# Sheet1-MCU.net
KiCad netlist of a schematic drawn in Altium Designer
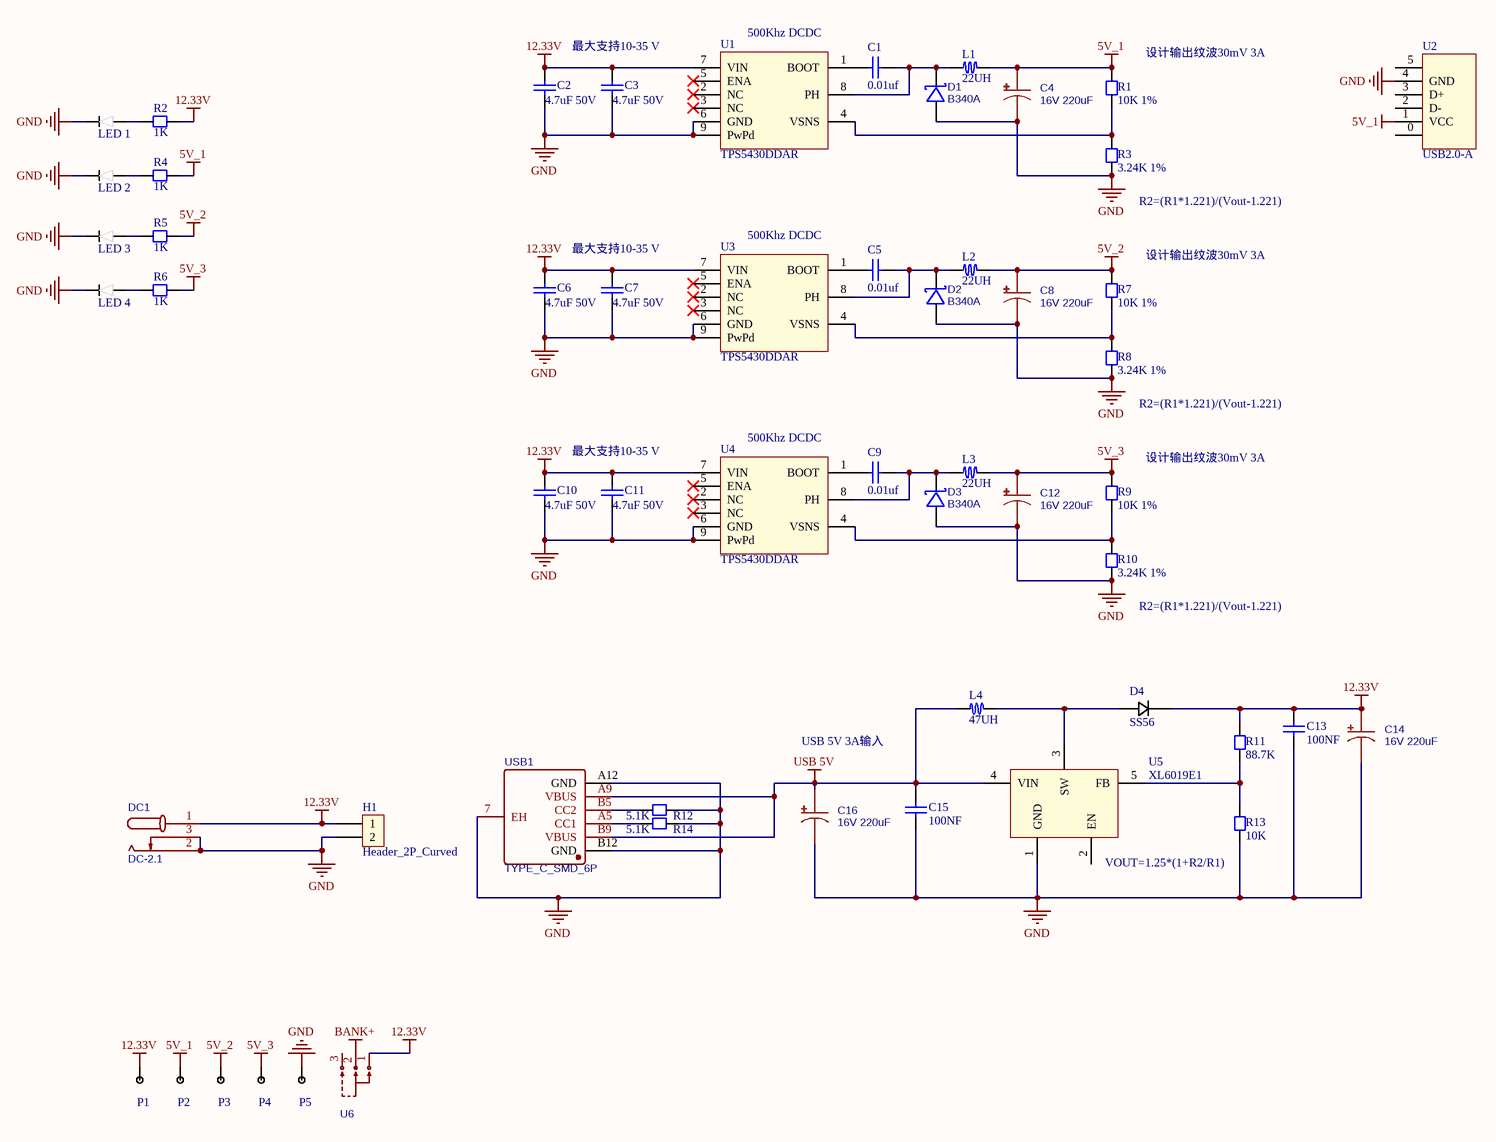
[diagram p0: Sheet1-MCU.SchDoc]

(export (version "E")
  (design (tool "Eeschema 10.0.6"))
  (components
    (comp (ref "C1")
      (value "0.01uf")
      (footprint "CC1608-0603")
      (description "贴片电容")
      (libsource (lib "tianxiaohua_Schlib") (part "Chip capacitor"))
    )
    (comp (ref "C2")
      (value "4.7uF 50V")
      (footprint "CC1608-0603")
      (description "贴片电容")
      (libsource (lib "tianxiaohua_Schlib") (part "Chip capacitor"))
    )
    (comp (ref "C3")
      (value "4.7uF 50V")
      (footprint "CC1608-0603")
      (description "贴片电容")
      (libsource (lib "tianxiaohua_Schlib") (part "Chip capacitor"))
    )
    (comp (ref "C4")
      (value "16V 220uF")
      (footprint "CAP-SMD_D6.3")
      (description "铝点解电容")
      (fields
        (field (name "BOM_SUPPLIER PART") "C413527")
        (field (name "BOM_MANUFACTURER PART") "EEEFP1C681AP")
        (field (name "CONTRIBUTOR") "LCSC")
      )
      (libsource (lib "base") (part "Cap ECAP SMD"))
    )
    (comp (ref "C5")
      (value "0.01uf")
      (footprint "CC1608-0603")
      (description "贴片电容")
      (libsource (lib "tianxiaohua_Schlib") (part "Chip capacitor"))
    )
    (comp (ref "C6")
      (value "4.7uF 50V")
      (footprint "CC1608-0603")
      (description "贴片电容")
      (libsource (lib "tianxiaohua_Schlib") (part "Chip capacitor"))
    )
    (comp (ref "C7")
      (value "4.7uF 50V")
      (footprint "CC1608-0603")
      (description "贴片电容")
      (libsource (lib "tianxiaohua_Schlib") (part "Chip capacitor"))
    )
    (comp (ref "C8")
      (value "16V 220uF")
      (footprint "CAP-SMD_D6.3")
      (description "铝点解电容")
      (fields
        (field (name "BOM_SUPPLIER PART") "C413527")
        (field (name "BOM_MANUFACTURER PART") "EEEFP1C681AP")
        (field (name "CONTRIBUTOR") "LCSC")
      )
      (libsource (lib "base") (part "Cap ECAP SMD"))
    )
    (comp (ref "C9")
      (value "0.01uf")
      (footprint "CC1608-0603")
      (description "贴片电容")
      (libsource (lib "tianxiaohua_Schlib") (part "Chip capacitor"))
    )
    (comp (ref "C10")
      (value "4.7uF 50V")
      (footprint "CC1608-0603")
      (description "贴片电容")
      (libsource (lib "tianxiaohua_Schlib") (part "Chip capacitor"))
    )
    (comp (ref "C11")
      (value "4.7uF 50V")
      (footprint "CC1608-0603")
      (description "贴片电容")
      (libsource (lib "tianxiaohua_Schlib") (part "Chip capacitor"))
    )
    (comp (ref "C12")
      (value "16V 220uF")
      (footprint "CAP-SMD_D6.3")
      (description "铝点解电容")
      (fields
        (field (name "BOM_SUPPLIER PART") "C413527")
        (field (name "BOM_MANUFACTURER PART") "EEEFP1C681AP")
        (field (name "CONTRIBUTOR") "LCSC")
      )
      (libsource (lib "base") (part "Cap ECAP SMD"))
    )
    (comp (ref "C13")
      (value "100NF")
      (footprint "CC1608-0603")
      (description "0603封装的电容")
      (fields (field (name "PUBLISHER") "Altium Limited"))
      (libsource (lib "base") (part "Cap Chip 0603"))
    )
    (comp (ref "C14")
      (value "16V 220uF")
      (footprint "CAP-SMD_D6.3")
      (description "铝点解电容")
      (fields
        (field (name "BOM_SUPPLIER PART") "C413527")
        (field (name "BOM_MANUFACTURER PART") "EEEFP1C681AP")
        (field (name "CONTRIBUTOR") "LCSC")
      )
      (libsource (lib "base") (part "Cap ECAP SMD"))
    )
    (comp (ref "C15")
      (value "100NF")
      (footprint "CC1608-0603")
      (description "0603封装的电容")
      (fields (field (name "PUBLISHER") "Altium Limited"))
      (libsource (lib "base") (part "Cap Chip 0603"))
    )
    (comp (ref "C16")
      (value "16V 220uF")
      (footprint "CAP-SMD_D6.3")
      (description "铝点解电容")
      (fields
        (field (name "BOM_SUPPLIER PART") "C413527")
        (field (name "BOM_MANUFACTURER PART") "EEEFP1C681AP")
        (field (name "CONTRIBUTOR") "LCSC")
      )
      (libsource (lib "base") (part "Cap ECAP SMD"))
    )
    (comp (ref "D1")
      (value "B340A")
      (footprint "DO-214 AA")
      (description "40V 3A 550mV@3A")
      (fields (field (name "BOM_SUPPLIER PART") "C64982"))
      (libsource (lib "transistor") (part "B340A"))
    )
    (comp (ref "D2")
      (value "B340A")
      (footprint "DO-214 AA")
      (description "40V 3A 550mV@3A")
      (fields (field (name "BOM_SUPPLIER PART") "C64982"))
      (libsource (lib "transistor") (part "B340A"))
    )
    (comp (ref "D3")
      (value "B340A")
      (footprint "DO-214 AA")
      (description "40V 3A 550mV@3A")
      (fields (field (name "BOM_SUPPLIER PART") "C64982"))
      (libsource (lib "transistor") (part "B340A"))
    )
    (comp (ref "D4")
      (value "SS56")
      (footprint "DO-214 AA")
      (description "肖特基二极管")
      (libsource (lib "transistor") (part "SS34"))
    )
    (comp (ref "DC1")
      (value "DC-2.1")
      (footprint "DC-IN-SMD_DC-050-25A")
      (description "DC贴片插座")
      (fields
        (field (name "BOM_SUPPLIER PART") "C707275")
        (field (name "BOM_MANUFACTURER PART") "DC-050-25A")
        (field (name "CONTRIBUTOR") "LCSC")
      )
      (libsource (lib "Connectors") (part "DC-050"))
    )
    (comp (ref "H1")
      (value "Header_2P_Curved")
      (footprint "Header_2_54_2PW")
      (description "弯的2P排针")
      (libsource (lib "base") (part "Header_2P_Curved"))
    )
    (comp (ref "L1")
      (value "22UH")
      (footprint "Inductor-1040")
      (description "1040封装 一体成型 贴片 功率电感")
      (libsource (lib "base") (part "Inductor-1040"))
    )
    (comp (ref "L2")
      (value "22UH")
      (footprint "Inductor-1040")
      (description "1040封装 一体成型 贴片 功率电感")
      (libsource (lib "base") (part "Inductor-1040"))
    )
    (comp (ref "L3")
      (value "22UH")
      (footprint "Inductor-1040")
      (description "1040封装 一体成型 贴片 功率电感")
      (libsource (lib "base") (part "Inductor-1040"))
    )
    (comp (ref "L4")
      (value "47UH")
      (footprint "Inductor-1040")
      (description "1040封装 一体成型 贴片 功率电感")
      (libsource (lib "base") (part "Inductor-1040"))
    )
    (comp (ref "LED 1") (value "LED 0603") (footprint "LED 0603") (libsource (lib "base") (part "LED 0603")))
    (comp (ref "LED 2") (value "LED 0603") (footprint "LED 0603") (libsource (lib "base") (part "LED 0603")))
    (comp (ref "LED 3") (value "LED 0603") (footprint "LED 0603") (libsource (lib "base") (part "LED 0603")))
    (comp (ref "LED 4") (value "LED 0603") (footprint "LED 0603") (libsource (lib "base") (part "LED 0603")))
    (comp (ref "P1")
      (value "pogopin")
      (footprint "pogopin")
      (description "插板式顶针 连接器弹簧天线插针SMT触点测试铜针双弹贴片式")
      (libsource (lib "Connectors") (part "pogopin"))
    )
    (comp (ref "P2")
      (value "pogopin")
      (footprint "pogopin")
      (description "插板式顶针 连接器弹簧天线插针SMT触点测试铜针双弹贴片式")
      (libsource (lib "Connectors") (part "pogopin"))
    )
    (comp (ref "P3")
      (value "pogopin")
      (footprint "pogopin")
      (description "插板式顶针 连接器弹簧天线插针SMT触点测试铜针双弹贴片式")
      (libsource (lib "Connectors") (part "pogopin"))
    )
    (comp (ref "P4")
      (value "pogopin")
      (footprint "pogopin")
      (description "插板式顶针 连接器弹簧天线插针SMT触点测试铜针双弹贴片式")
      (libsource (lib "Connectors") (part "pogopin"))
    )
    (comp (ref "P5")
      (value "pogopin")
      (footprint "pogopin")
      (description "插板式顶针 连接器弹簧天线插针SMT触点测试铜针双弹贴片式")
      (libsource (lib "Connectors") (part "pogopin"))
    )
    (comp (ref "R1")
      (value "10K 1%")
      (footprint "CR1608-0603")
      (description "贴片电阻")
      (libsource (lib "tianxiaohua_Schlib") (part "Chip resistor"))
    )
    (comp (ref "R2")
      (value "1K")
      (footprint "CR1608-0603")
      (description "0603封装电阻")
      (fields (field (name "PUBLISHER") "Altium Limited"))
      (libsource (lib "base") (part "Resistor Chip 0603"))
    )
    (comp (ref "R3")
      (value "3.24K 1%")
      (footprint "CR1608-0603")
      (description "贴片电阻")
      (libsource (lib "tianxiaohua_Schlib") (part "Chip resistor"))
    )
    (comp (ref "R4")
      (value "1K")
      (footprint "CR1608-0603")
      (description "0603封装电阻")
      (fields (field (name "PUBLISHER") "Altium Limited"))
      (libsource (lib "base") (part "Resistor Chip 0603"))
    )
    (comp (ref "R5")
      (value "1K")
      (footprint "CR1608-0603")
      (description "0603封装电阻")
      (fields (field (name "PUBLISHER") "Altium Limited"))
      (libsource (lib "base") (part "Resistor Chip 0603"))
    )
    (comp (ref "R6")
      (value "1K")
      (footprint "CR1608-0603")
      (description "0603封装电阻")
      (fields (field (name "PUBLISHER") "Altium Limited"))
      (libsource (lib "base") (part "Resistor Chip 0603"))
    )
    (comp (ref "R7")
      (value "10K 1%")
      (footprint "CR1608-0603")
      (description "贴片电阻")
      (libsource (lib "tianxiaohua_Schlib") (part "Chip resistor"))
    )
    (comp (ref "R8")
      (value "3.24K 1%")
      (footprint "CR1608-0603")
      (description "贴片电阻")
      (libsource (lib "tianxiaohua_Schlib") (part "Chip resistor"))
    )
    (comp (ref "R9")
      (value "10K 1%")
      (footprint "CR1608-0603")
      (description "贴片电阻")
      (libsource (lib "tianxiaohua_Schlib") (part "Chip resistor"))
    )
    (comp (ref "R10")
      (value "3.24K 1%")
      (footprint "CR1608-0603")
      (description "贴片电阻")
      (libsource (lib "tianxiaohua_Schlib") (part "Chip resistor"))
    )
    (comp (ref "R11")
      (value "88.7K")
      (footprint "CR1608-0603")
      (description "0603封装电阻")
      (fields (field (name "PUBLISHER") "Altium Limited"))
      (libsource (lib "") (part "Resistor Chip 0603_2"))
    )
    (comp (ref "R12")
      (value "5.1K")
      (footprint "CR1608-0603")
      (description "0603封装电阻")
      (fields (field (name "PUBLISHER") "Altium Limited"))
      (libsource (lib "") (part "Resistor Chip 0603_1"))
    )
    (comp (ref "R13")
      (value "10K")
      (footprint "CR1608-0603")
      (description "0603封装电阻")
      (fields (field (name "PUBLISHER") "Altium Limited"))
      (libsource (lib "") (part "Resistor Chip 0603_2"))
    )
    (comp (ref "R14")
      (value "5.1K")
      (footprint "CR1608-0603")
      (description "0603封装电阻")
      (fields (field (name "PUBLISHER") "Altium Limited"))
      (libsource (lib "") (part "Resistor Chip 0603_1"))
    )
    (comp (ref "U1")
      (value "TPS5430DDAR")
      (footprint "SOIC-8-E")
      (description "宽电压DCDC降压IC")
      (libsource (lib "power-chip") (part "TPS5430DDAR"))
    )
    (comp (ref "U2")
      (value "USB2.0-A")
      (footprint "USB2.0-A")
      (description "USB母座")
      (libsource (lib "Connectors") (part "USB2.0-A"))
    )
    (comp (ref "U3")
      (value "TPS5430DDAR")
      (footprint "SOIC-8-E")
      (description "宽电压DCDC降压IC")
      (libsource (lib "power-chip") (part "TPS5430DDAR"))
    )
    (comp (ref "U4")
      (value "TPS5430DDAR")
      (footprint "SOIC-8-E")
      (description "宽电压DCDC降压IC")
      (libsource (lib "power-chip") (part "TPS5430DDAR"))
    )
    (comp (ref "U5")
      (value "XL6019E1")
      (footprint "TO-263-5")
      (description "升压芯片 5A最大输出")
      (libsource (lib "power-chip") (part "XL6019E1"))
    )
    (comp (ref "U6")
      (value "HX SS12D10G4")
      (footprint "SW-TH_3P-SS12D06")
      (fields (field (name "BOM_SUPPLIER PART") "C5149841") (field (name "CONTRIBUTOR") "lcsc"))
      (libsource (lib "base") (part "SW-TH_3P-SS12D06"))
    )
    (comp (ref "USB1")
      (value "TYPE_C_SMD_6P")
      (footprint "TYPE-C-SMD_TYPE-C-6P")
      (fields (field (name "CONTRIBUTOR") "LCSC"))
      (libsource (lib "Connectors") (part "TYPE_C_SMD_6P"))
    )
  )
  (nets
    (net (code "1") (name "5V_1") (class "Default")
      (node (ref "C4") (pin "1") (pinfunction "1_1") (pintype "passive"))
      (node (ref "L1") (pin "2") (pinfunction "2_2") (pintype "passive"))
      (node (ref "P2") (pin "1") (pinfunction "1_1") (pintype "passive"))
      (node (ref "R1") (pin "2") (pinfunction "2_2") (pintype "passive"))
      (node (ref "R4") (pin "1") (pinfunction "1_1") (pintype "passive"))
      (node (ref "U2") (pin "1") (pinfunction "VCC_1") (pintype "passive"))
    )
    (net (code "2") (name "5V_2") (class "Default")
      (node (ref "C8") (pin "1") (pinfunction "1_1") (pintype "passive"))
      (node (ref "L2") (pin "2") (pinfunction "2_2") (pintype "passive"))
      (node (ref "P3") (pin "1") (pinfunction "1_1") (pintype "passive"))
      (node (ref "R5") (pin "1") (pinfunction "1_1") (pintype "passive"))
      (node (ref "R7") (pin "2") (pinfunction "2_2") (pintype "passive"))
    )
    (net (code "3") (name "5V_3") (class "Default")
      (node (ref "C12") (pin "1") (pinfunction "1_1") (pintype "passive"))
      (node (ref "L3") (pin "2") (pinfunction "2_2") (pintype "passive"))
      (node (ref "P4") (pin "1") (pinfunction "1_1") (pintype "passive"))
      (node (ref "R6") (pin "1") (pinfunction "1_1") (pintype "passive"))
      (node (ref "R9") (pin "2") (pinfunction "2_2") (pintype "passive"))
    )
    (net (code "4") (name "12.33V") (class "Default")
      (node (ref "C10") (pin "1") (pinfunction "1_1") (pintype "passive"))
      (node (ref "C11") (pin "1") (pinfunction "1_1") (pintype "passive"))
      (node (ref "C13") (pin "2") (pinfunction "2_2") (pintype "passive"))
      (node (ref "C14") (pin "1") (pinfunction "1_1") (pintype "passive"))
      (node (ref "C2") (pin "1") (pinfunction "1_1") (pintype "passive"))
      (node (ref "C3") (pin "1") (pinfunction "1_1") (pintype "passive"))
      (node (ref "C6") (pin "1") (pinfunction "1_1") (pintype "passive"))
      (node (ref "C7") (pin "1") (pinfunction "1_1") (pintype "passive"))
      (node (ref "D4") (pin "1") (pinfunction "K_1") (pintype "passive"))
      (node (ref "DC1") (pin "1") (pinfunction "1_1") (pintype "passive"))
      (node (ref "H1") (pin "1") (pinfunction "1_1") (pintype "passive"))
      (node (ref "P1") (pin "1") (pinfunction "1_1") (pintype "passive"))
      (node (ref "R11") (pin "2") (pinfunction "2_2") (pintype "passive"))
      (node (ref "R2") (pin "1") (pinfunction "1_1") (pintype "passive"))
      (node (ref "U1") (pin "7") (pinfunction "VIN_7") (pintype "passive"))
      (node (ref "U3") (pin "7") (pinfunction "VIN_7") (pintype "passive"))
      (node (ref "U4") (pin "7") (pinfunction "VIN_7") (pintype "passive"))
      (node (ref "U6") (pin "1") (pinfunction "1_1") (pintype "passive"))
    )
    (net (code "5") (name "BANK+") (class "Default")
      (node (ref "U6") (pin "2") (pinfunction "2_2") (pintype "passive"))
    )
    (net (code "6") (name "GND") (class "Default")
      (node (ref "C10") (pin "2") (pinfunction "2_2") (pintype "passive"))
      (node (ref "C11") (pin "2") (pinfunction "2_2") (pintype "passive"))
      (node (ref "C12") (pin "2") (pinfunction "2_2") (pintype "passive"))
      (node (ref "C13") (pin "1") (pinfunction "1_1") (pintype "passive"))
      (node (ref "C14") (pin "2") (pinfunction "2_2") (pintype "passive"))
      (node (ref "C15") (pin "1") (pinfunction "1_1") (pintype "passive"))
      (node (ref "C16") (pin "2") (pinfunction "2_2") (pintype "passive"))
      (node (ref "C2") (pin "2") (pinfunction "2_2") (pintype "passive"))
      (node (ref "C3") (pin "2") (pinfunction "2_2") (pintype "passive"))
      (node (ref "C4") (pin "2") (pinfunction "2_2") (pintype "passive"))
      (node (ref "C6") (pin "2") (pinfunction "2_2") (pintype "passive"))
      (node (ref "C7") (pin "2") (pinfunction "2_2") (pintype "passive"))
      (node (ref "C8") (pin "2") (pinfunction "2_2") (pintype "passive"))
      (node (ref "D1") (pin "2") (pinfunction "A_2") (pintype "passive"))
      (node (ref "D2") (pin "2") (pinfunction "A_2") (pintype "passive"))
      (node (ref "D3") (pin "2") (pinfunction "A_2") (pintype "passive"))
      (node (ref "DC1") (pin "2") (pinfunction "2_2") (pintype "passive"))
      (node (ref "DC1") (pin "3") (pinfunction "3_3") (pintype "passive"))
      (node (ref "H1") (pin "2") (pinfunction "2_2") (pintype "passive"))
      (node (ref "LED 1") (pin "2") (pinfunction "2_2") (pintype "passive"))
      (node (ref "LED 2") (pin "2") (pinfunction "2_2") (pintype "passive"))
      (node (ref "LED 3") (pin "2") (pinfunction "2_2") (pintype "passive"))
      (node (ref "LED 4") (pin "2") (pinfunction "2_2") (pintype "passive"))
      (node (ref "P5") (pin "1") (pinfunction "1_1") (pintype "passive"))
      (node (ref "R10") (pin "1") (pinfunction "1_1") (pintype "passive"))
      (node (ref "R12") (pin "2") (pinfunction "2_2") (pintype "passive"))
      (node (ref "R13") (pin "1") (pinfunction "1_1") (pintype "passive"))
      (node (ref "R14") (pin "2") (pinfunction "2_2") (pintype "passive"))
      (node (ref "R3") (pin "1") (pinfunction "1_1") (pintype "passive"))
      (node (ref "R8") (pin "1") (pinfunction "1_1") (pintype "passive"))
      (node (ref "U1") (pin "6") (pinfunction "GND_6") (pintype "passive"))
      (node (ref "U1") (pin "9") (pinfunction "PwPd_9") (pintype "passive"))
      (node (ref "U2") (pin "4") (pinfunction "GND_4") (pintype "passive"))
      (node (ref "U3") (pin "6") (pinfunction "GND_6") (pintype "passive"))
      (node (ref "U3") (pin "9") (pinfunction "PwPd_9") (pintype "passive"))
      (node (ref "U4") (pin "6") (pinfunction "GND_6") (pintype "passive"))
      (node (ref "U4") (pin "9") (pinfunction "PwPd_9") (pintype "passive"))
      (node (ref "U5") (pin "1") (pinfunction "GND_1") (pintype "passive"))
      (node (ref "USB1") (pin "7") (pinfunction "EH_7") (pintype "passive"))
      (node (ref "USB1") (pin "A12") (pinfunction "GND_A12") (pintype "passive"))
      (node (ref "USB1") (pin "B12") (pinfunction "GND_B12") (pintype "passive"))
    )
    (net (code "7") (name "Net-(D1-K)") (class "Default")
      (node (ref "C1") (pin "2") (pinfunction "2_2") (pintype "passive"))
      (node (ref "D1") (pin "1") (pinfunction "K_1") (pintype "passive"))
      (node (ref "L1") (pin "1") (pinfunction "1_1") (pintype "passive"))
      (node (ref "U1") (pin "8") (pinfunction "PH_8") (pintype "passive"))
    )
    (net (code "8") (name "Net-(D2-K)") (class "Default")
      (node (ref "C5") (pin "2") (pinfunction "2_2") (pintype "passive"))
      (node (ref "D2") (pin "1") (pinfunction "K_1") (pintype "passive"))
      (node (ref "L2") (pin "1") (pinfunction "1_1") (pintype "passive"))
      (node (ref "U3") (pin "8") (pinfunction "PH_8") (pintype "passive"))
    )
    (net (code "9") (name "Net-(D3-K)") (class "Default")
      (node (ref "C9") (pin "2") (pinfunction "2_2") (pintype "passive"))
      (node (ref "D3") (pin "1") (pinfunction "K_1") (pintype "passive"))
      (node (ref "L3") (pin "1") (pinfunction "1_1") (pintype "passive"))
      (node (ref "U4") (pin "8") (pinfunction "PH_8") (pintype "passive"))
    )
    (net (code "10") (name "Net-(D4-A)") (class "Default")
      (node (ref "D4") (pin "2") (pinfunction "A_2") (pintype "passive"))
      (node (ref "L4") (pin "2") (pinfunction "2_2") (pintype "passive"))
      (node (ref "U5") (pin "3") (pinfunction "SW_3") (pintype "passive"))
    )
    (net (code "11") (name "Net-(LED 1-Pad1)") (class "Default")
      (node (ref "LED 1") (pin "1") (pinfunction "1_1") (pintype "passive"))
      (node (ref "R2") (pin "2") (pinfunction "2_2") (pintype "passive"))
    )
    (net (code "12") (name "Net-(LED 2-Pad1)") (class "Default")
      (node (ref "LED 2") (pin "1") (pinfunction "1_1") (pintype "passive"))
      (node (ref "R4") (pin "2") (pinfunction "2_2") (pintype "passive"))
    )
    (net (code "13") (name "Net-(LED 3-Pad1)") (class "Default")
      (node (ref "LED 3") (pin "1") (pinfunction "1_1") (pintype "passive"))
      (node (ref "R5") (pin "2") (pinfunction "2_2") (pintype "passive"))
    )
    (net (code "14") (name "Net-(LED 4-Pad1)") (class "Default")
      (node (ref "LED 4") (pin "1") (pinfunction "1_1") (pintype "passive"))
      (node (ref "R6") (pin "2") (pinfunction "2_2") (pintype "passive"))
    )
    (net (code "15") (name "Net-(U1-BOOT)") (class "Default")
      (node (ref "C1") (pin "1") (pinfunction "1_1") (pintype "passive"))
      (node (ref "U1") (pin "1") (pinfunction "BOOT_1") (pintype "passive"))
    )
    (net (code "16") (name "Net-(U1-VSNS)") (class "Default")
      (node (ref "R1") (pin "1") (pinfunction "1_1") (pintype "passive"))
      (node (ref "R3") (pin "2") (pinfunction "2_2") (pintype "passive"))
      (node (ref "U1") (pin "4") (pinfunction "VSNS_4") (pintype "passive"))
    )
    (net (code "17") (name "Net-(U3-BOOT)") (class "Default")
      (node (ref "C5") (pin "1") (pinfunction "1_1") (pintype "passive"))
      (node (ref "U3") (pin "1") (pinfunction "BOOT_1") (pintype "passive"))
    )
    (net (code "18") (name "Net-(U3-VSNS)") (class "Default")
      (node (ref "R7") (pin "1") (pinfunction "1_1") (pintype "passive"))
      (node (ref "R8") (pin "2") (pinfunction "2_2") (pintype "passive"))
      (node (ref "U3") (pin "4") (pinfunction "VSNS_4") (pintype "passive"))
    )
    (net (code "19") (name "Net-(U4-BOOT)") (class "Default")
      (node (ref "C9") (pin "1") (pinfunction "1_1") (pintype "passive"))
      (node (ref "U4") (pin "1") (pinfunction "BOOT_1") (pintype "passive"))
    )
    (net (code "20") (name "Net-(U4-VSNS)") (class "Default")
      (node (ref "R10") (pin "2") (pinfunction "2_2") (pintype "passive"))
      (node (ref "R9") (pin "1") (pinfunction "1_1") (pintype "passive"))
      (node (ref "U4") (pin "4") (pinfunction "VSNS_4") (pintype "passive"))
    )
    (net (code "21") (name "Net-(U5-FB)") (class "Default")
      (node (ref "R11") (pin "1") (pinfunction "1_1") (pintype "passive"))
      (node (ref "R13") (pin "2") (pinfunction "2_2") (pintype "passive"))
      (node (ref "U5") (pin "5") (pinfunction "FB_5") (pintype "passive"))
    )
    (net (code "22") (name "Net-(USB1-CC1)") (class "Default")
      (node (ref "R14") (pin "1") (pinfunction "1_1") (pintype "passive"))
      (node (ref "USB1") (pin "A5") (pinfunction "CC1_A5") (pintype "passive"))
    )
    (net (code "23") (name "Net-(USB1-CC2)") (class "Default")
      (node (ref "R12") (pin "1") (pinfunction "1_1") (pintype "passive"))
      (node (ref "USB1") (pin "B5") (pinfunction "CC2_B5") (pintype "passive"))
    )
    (net (code "24") (name "USB 5V") (class "Default")
      (node (ref "C15") (pin "2") (pinfunction "2_2") (pintype "passive"))
      (node (ref "C16") (pin "1") (pinfunction "1_1") (pintype "passive"))
      (node (ref "L4") (pin "1") (pinfunction "1_1") (pintype "passive"))
      (node (ref "U5") (pin "4") (pinfunction "VIN_4") (pintype "passive"))
      (node (ref "USB1") (pin "A9") (pinfunction "VBUS_A9") (pintype "passive"))
      (node (ref "USB1") (pin "B9") (pinfunction "VBUS_B9") (pintype "passive"))
    )
    (net (code "25") (name "unconnected-(U1-ENA-Pad5)") (class "Default")
      (node (ref "U1") (pin "5") (pinfunction "ENA_5") (pintype "passive+no_connect"))
    )
    (net (code "26") (name "unconnected-(U1-NC-Pad2)") (class "Default")
      (node (ref "U1") (pin "2") (pinfunction "NC_2") (pintype "passive+no_connect"))
    )
    (net (code "27") (name "unconnected-(U1-NC-Pad3)") (class "Default")
      (node (ref "U1") (pin "3") (pinfunction "NC_3") (pintype "passive+no_connect"))
    )
    (net (code "28") (name "unconnected-(U2-5-Pad0)") (class "Default")
      (node (ref "U2") (pin "0") (pinfunction "5_0") (pintype "passive"))
    )
    (net (code "29") (name "unconnected-(U2-6-Pad5)") (class "Default")
      (node (ref "U2") (pin "5") (pinfunction "6_5") (pintype "passive"))
    )
    (net (code "30") (name "unconnected-(U2-D+-Pad3)") (class "Default")
      (node (ref "U2") (pin "3") (pinfunction "D+_3") (pintype "passive"))
    )
    (net (code "31") (name "unconnected-(U2-D--Pad2)") (class "Default")
      (node (ref "U2") (pin "2") (pinfunction "D-_2") (pintype "passive"))
    )
    (net (code "32") (name "unconnected-(U3-ENA-Pad5)") (class "Default")
      (node (ref "U3") (pin "5") (pinfunction "ENA_5") (pintype "passive+no_connect"))
    )
    (net (code "33") (name "unconnected-(U3-NC-Pad2)") (class "Default")
      (node (ref "U3") (pin "2") (pinfunction "NC_2") (pintype "passive+no_connect"))
    )
    (net (code "34") (name "unconnected-(U3-NC-Pad3)") (class "Default")
      (node (ref "U3") (pin "3") (pinfunction "NC_3") (pintype "passive+no_connect"))
    )
    (net (code "35") (name "unconnected-(U4-ENA-Pad5)") (class "Default")
      (node (ref "U4") (pin "5") (pinfunction "ENA_5") (pintype "passive+no_connect"))
    )
    (net (code "36") (name "unconnected-(U4-NC-Pad2)") (class "Default")
      (node (ref "U4") (pin "2") (pinfunction "NC_2") (pintype "passive+no_connect"))
    )
    (net (code "37") (name "unconnected-(U4-NC-Pad3)") (class "Default")
      (node (ref "U4") (pin "3") (pinfunction "NC_3") (pintype "passive+no_connect"))
    )
    (net (code "38") (name "unconnected-(U5-EN-Pad2)") (class "Default")
      (node (ref "U5") (pin "2") (pinfunction "EN_2") (pintype "passive"))
    )
    (net (code "39") (name "unconnected-(U6-Pad3)") (class "Default")
      (node (ref "U6") (pin "3") (pinfunction "3_3") (pintype "passive"))
    )
  )
)
